# Ears_0603.net
KiCad netlist of a schematic drawn in EAGLE
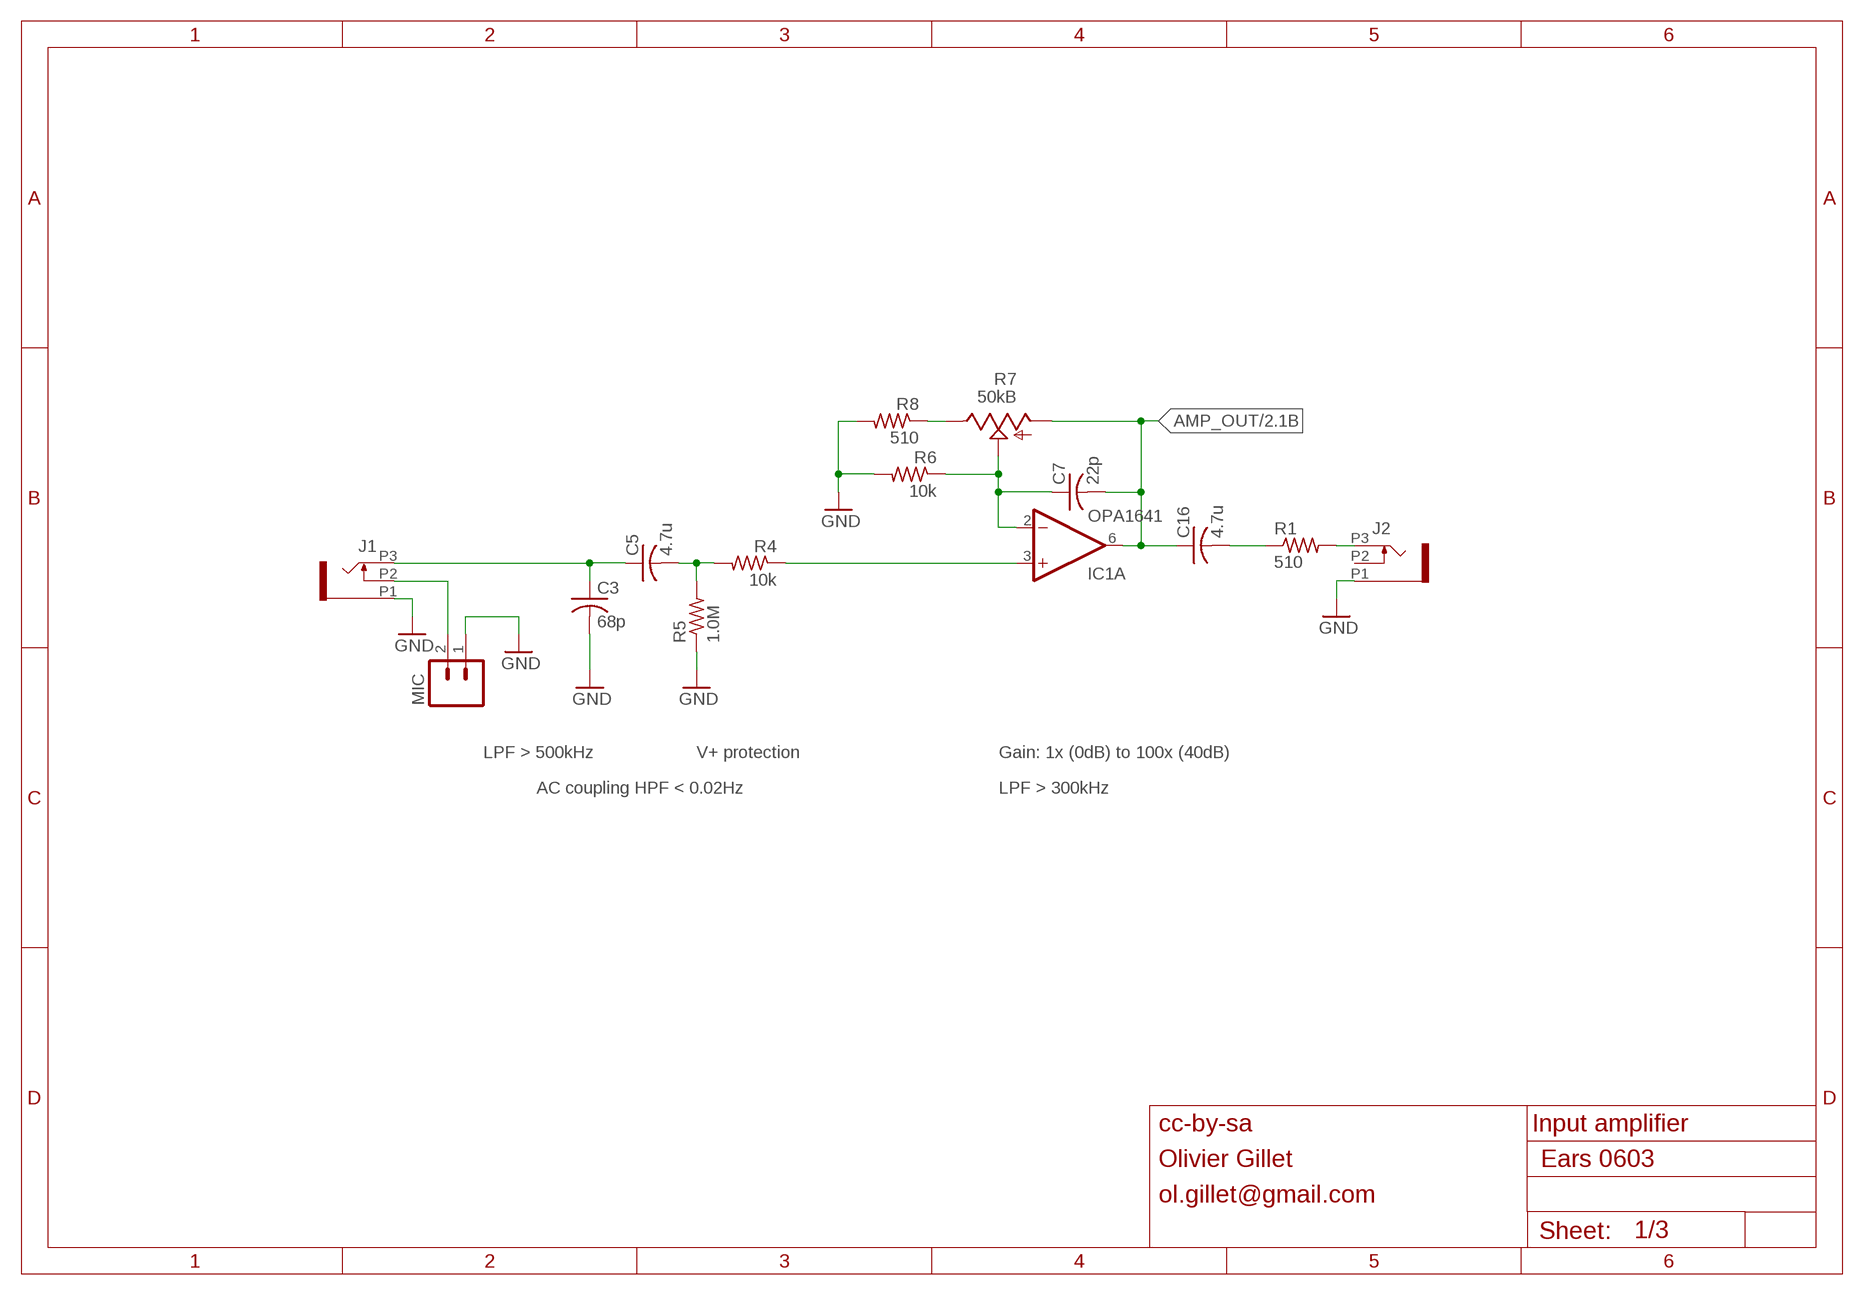
[diagram p0: schematic, sheet 1]
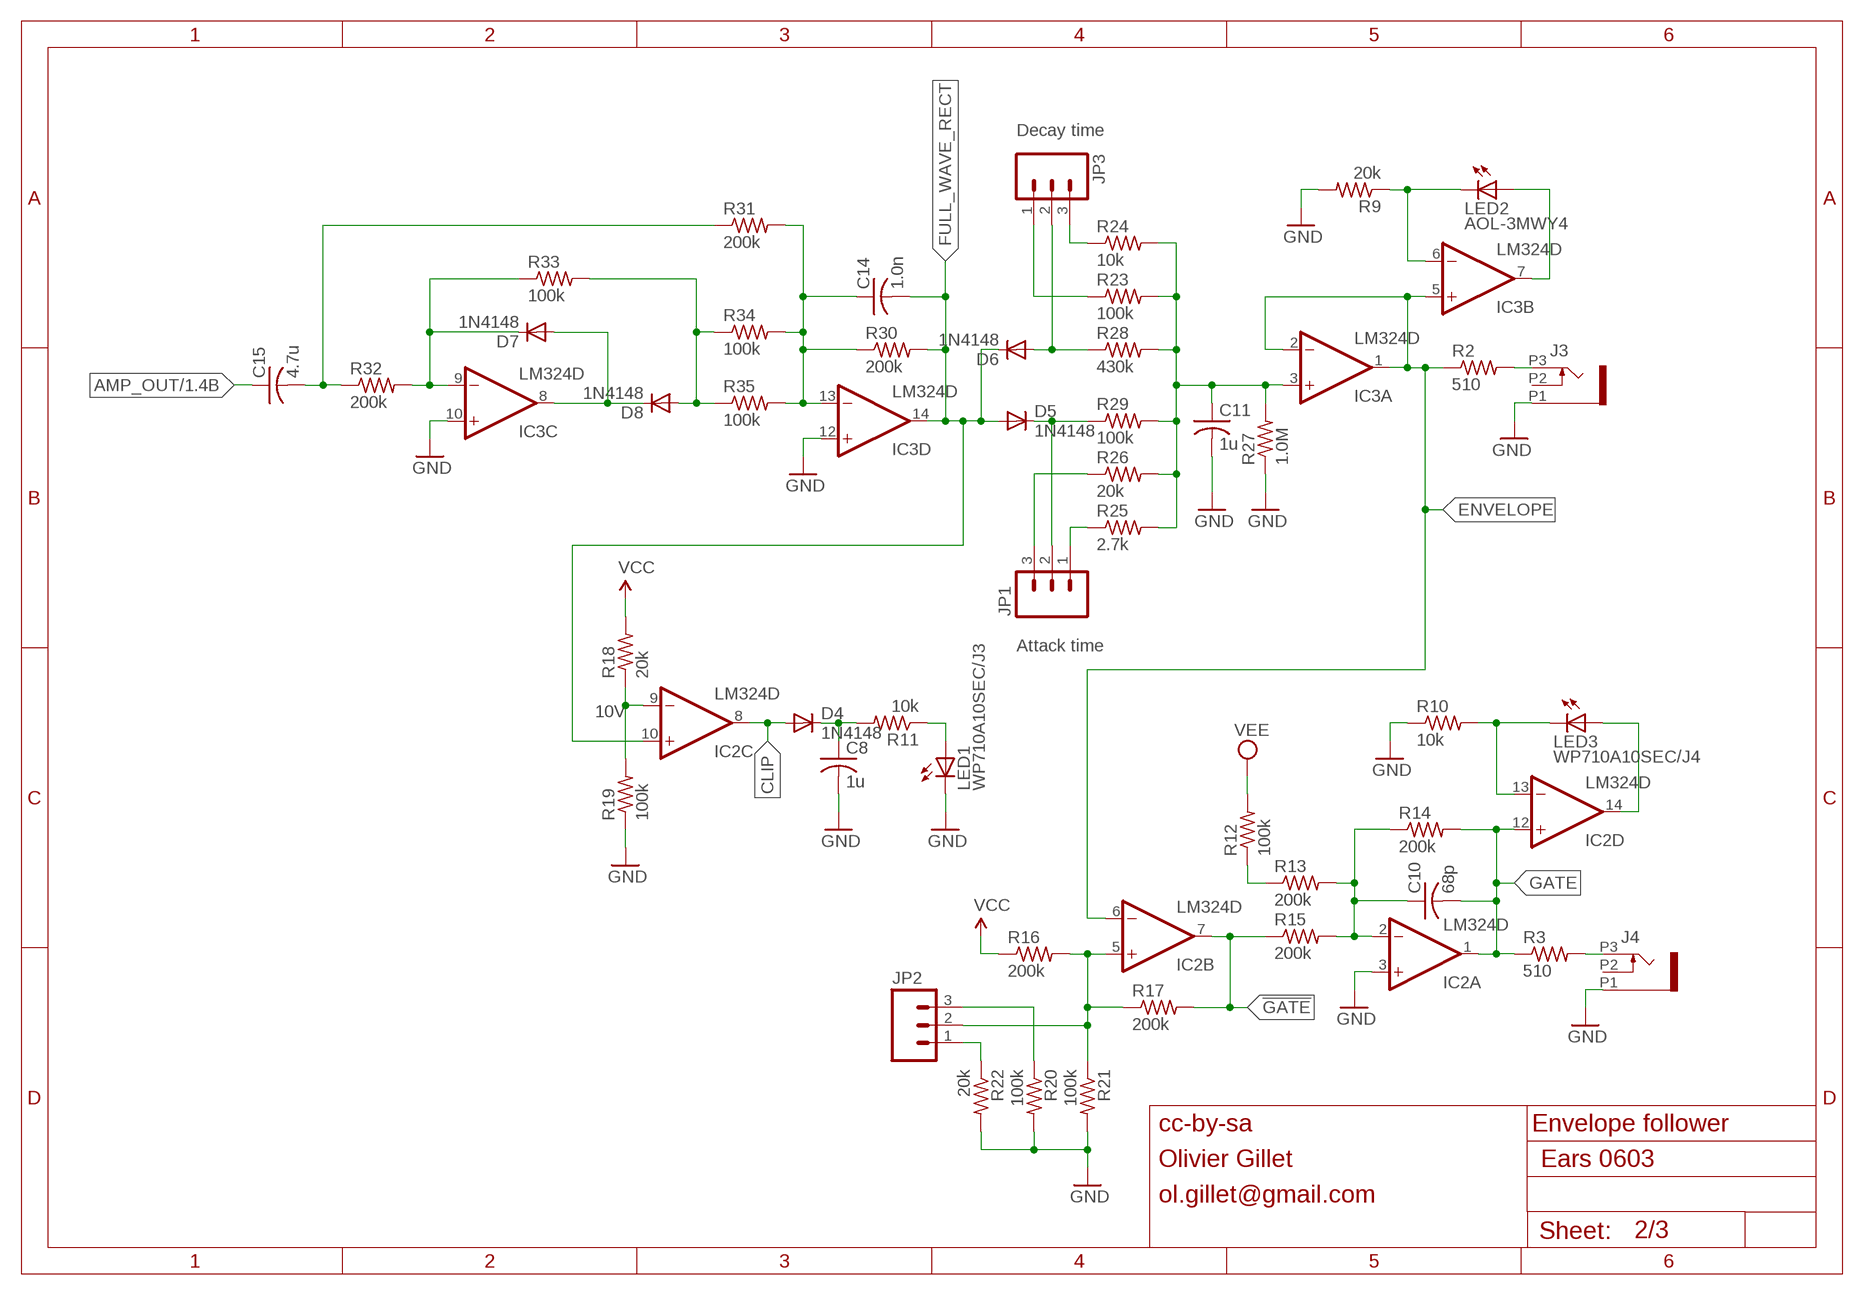
[diagram p1: schematic, sheet 2]
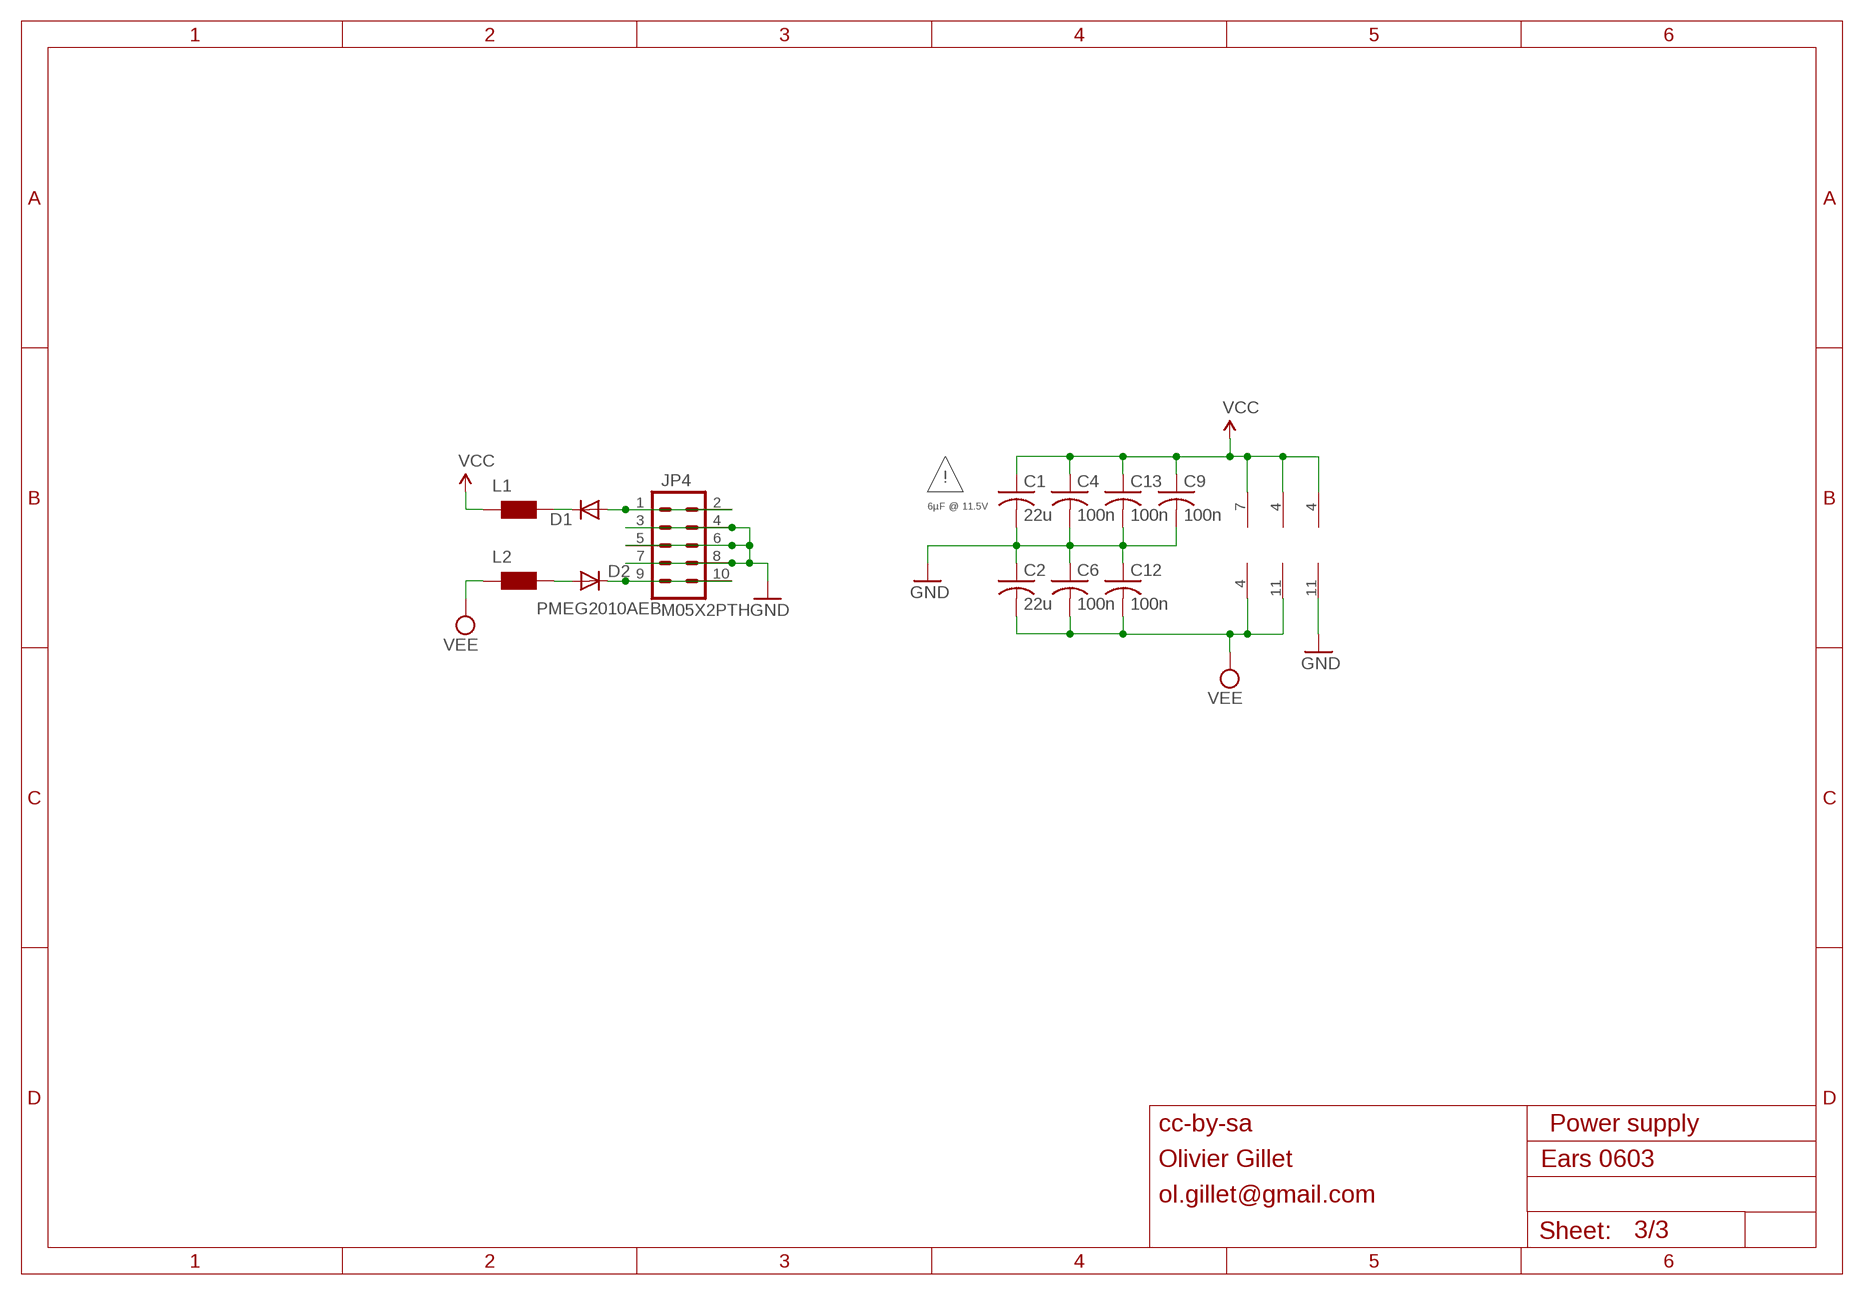
[diagram p2: schematic, sheet 3]

(export (version "E")
  (design (tool "Eeschema 10.0.6"))
  (components
    (comp (ref "C8")
      (value "1u")
      (footprint "eagle-import:C0603")
      (libsource (lib "eagle-import") (part "C-USC0603"))
    )
    (comp (ref "C10")
      (value "68p")
      (footprint "eagle-import:C0603")
      (libsource (lib "eagle-import") (part "C-USC0603"))
    )
    (comp (ref "C11")
      (value "1u")
      (footprint "eagle-import:C0603")
      (libsource (lib "eagle-import") (part "C-USC0603"))
    )
    (comp (ref "C14")
      (value "1.0n")
      (footprint "eagle-import:C0603")
      (libsource (lib "eagle-import") (part "C-USC0603"))
    )
    (comp (ref "C15")
      (value "4.7u")
      (footprint "eagle-import:C0603")
      (libsource (lib "eagle-import") (part "C-USC0603"))
    )
    (comp (ref "D4")
      (value "1N4148")
      (footprint "eagle-import:SOD323-W")
      (libsource (lib "eagle-import") (part "DIODE-SOD323-W"))
    )
    (comp (ref "D5")
      (value "1N4148")
      (footprint "eagle-import:SOD323-W")
      (libsource (lib "eagle-import") (part "DIODE-SOD323-W"))
    )
    (comp (ref "D6")
      (value "1N4148")
      (footprint "eagle-import:SOD323-W")
      (libsource (lib "eagle-import") (part "DIODE-SOD323-W"))
    )
    (comp (ref "D7")
      (value "1N4148")
      (footprint "eagle-import:SOD323-W")
      (libsource (lib "eagle-import") (part "DIODE-SOD323-W"))
    )
    (comp (ref "D8")
      (value "1N4148")
      (footprint "eagle-import:SOD323-W")
      (libsource (lib "eagle-import") (part "DIODE-SOD323-W"))
    )
    (comp (ref "IC2")
      (value "LM324D")
      (footprint "eagle-import:SO14")
      (libsource (lib "eagle-import") (part "LM324D"))
    )
    (comp (ref "IC3")
      (value "LM324D")
      (footprint "eagle-import:SO14")
      (libsource (lib "eagle-import") (part "LM324D"))
    )
    (comp (ref "J3")
      (value "PJ301_THONKICONN6")
      (footprint "eagle-import:WQP_PJ_301M6")
      (libsource (lib "eagle-import") (part "PJ301_THONKICONN6"))
    )
    (comp (ref "J4")
      (value "PJ301_THONKICONN6")
      (footprint "eagle-import:WQP_PJ_301M6")
      (libsource (lib "eagle-import") (part "PJ301_THONKICONN6"))
    )
    (comp (ref "JP1")
      (value "M03PTH")
      (footprint "eagle-import:1X03")
      (libsource (lib "eagle-import") (part "M03PTH"))
    )
    (comp (ref "JP2")
      (value "M03PTH")
      (footprint "eagle-import:1X03")
      (libsource (lib "eagle-import") (part "M03PTH"))
    )
    (comp (ref "JP3")
      (value "M03PTH")
      (footprint "eagle-import:1X03")
      (libsource (lib "eagle-import") (part "M03PTH"))
    )
    (comp (ref "LED1")
      (value "WP710A10SEC/J3")
      (footprint "eagle-import:LED3MM")
      (libsource (lib "eagle-import") (part "LED3MM"))
    )
    (comp (ref "LED2")
      (value "AOL-3MWY4")
      (footprint "eagle-import:LED3MM")
      (libsource (lib "eagle-import") (part "LED3MM"))
    )
    (comp (ref "LED3")
      (value "WP710A10SEC/J4")
      (footprint "eagle-import:LED3MM")
      (libsource (lib "eagle-import") (part "LED3MM"))
    )
    (comp (ref "R2")
      (value "510")
      (footprint "eagle-import:R0603")
      (libsource (lib "eagle-import") (part "R-US_R0603"))
    )
    (comp (ref "R3")
      (value "510")
      (footprint "eagle-import:R0603")
      (libsource (lib "eagle-import") (part "R-US_R0603"))
    )
    (comp (ref "R9")
      (value "20k")
      (footprint "eagle-import:R0603")
      (libsource (lib "eagle-import") (part "R-US_R0603"))
    )
    (comp (ref "R10")
      (value "10k")
      (footprint "eagle-import:R0603")
      (libsource (lib "eagle-import") (part "R-US_R0603"))
    )
    (comp (ref "R11")
      (value "10k")
      (footprint "eagle-import:R0603")
      (libsource (lib "eagle-import") (part "R-US_R0603"))
    )
    (comp (ref "R12")
      (value "100k")
      (footprint "eagle-import:R0603")
      (libsource (lib "eagle-import") (part "R-US_R0603"))
    )
    (comp (ref "R13")
      (value "200k")
      (footprint "eagle-import:R0603")
      (libsource (lib "eagle-import") (part "R-US_R0603"))
    )
    (comp (ref "R14")
      (value "200k")
      (footprint "eagle-import:R0603")
      (libsource (lib "eagle-import") (part "R-US_R0603"))
    )
    (comp (ref "R15")
      (value "200k")
      (footprint "eagle-import:R0603")
      (libsource (lib "eagle-import") (part "R-US_R0603"))
    )
    (comp (ref "R16")
      (value "200k")
      (footprint "eagle-import:R0603")
      (libsource (lib "eagle-import") (part "R-US_R0603"))
    )
    (comp (ref "R17")
      (value "200k")
      (footprint "eagle-import:R0603")
      (libsource (lib "eagle-import") (part "R-US_R0603"))
    )
    (comp (ref "R18")
      (value "20k")
      (footprint "eagle-import:R0603")
      (libsource (lib "eagle-import") (part "R-US_R0603"))
    )
    (comp (ref "R19")
      (value "100k")
      (footprint "eagle-import:R0603")
      (libsource (lib "eagle-import") (part "R-US_R0603"))
    )
    (comp (ref "R20")
      (value "100k")
      (footprint "eagle-import:R0603")
      (libsource (lib "eagle-import") (part "R-US_R0603"))
    )
    (comp (ref "R21")
      (value "100k")
      (footprint "eagle-import:R0603")
      (libsource (lib "eagle-import") (part "R-US_R0603"))
    )
    (comp (ref "R22")
      (value "20k")
      (footprint "eagle-import:R0603")
      (libsource (lib "eagle-import") (part "R-US_R0603"))
    )
    (comp (ref "R23")
      (value "100k")
      (footprint "eagle-import:R0603")
      (libsource (lib "eagle-import") (part "R-US_R0603"))
    )
    (comp (ref "R24")
      (value "10k")
      (footprint "eagle-import:R0603")
      (libsource (lib "eagle-import") (part "R-US_R0603"))
    )
    (comp (ref "R25")
      (value "2.7k")
      (footprint "eagle-import:R0603")
      (libsource (lib "eagle-import") (part "R-US_R0603"))
    )
    (comp (ref "R26")
      (value "20k")
      (footprint "eagle-import:R0603")
      (libsource (lib "eagle-import") (part "R-US_R0603"))
    )
    (comp (ref "R27")
      (value "1.0M")
      (footprint "eagle-import:R0603")
      (libsource (lib "eagle-import") (part "R-US_R0603"))
    )
    (comp (ref "R28")
      (value "430k")
      (footprint "eagle-import:R0603")
      (libsource (lib "eagle-import") (part "R-US_R0603"))
    )
    (comp (ref "R29")
      (value "100k")
      (footprint "eagle-import:R0603")
      (libsource (lib "eagle-import") (part "R-US_R0603"))
    )
    (comp (ref "R30")
      (value "200k")
      (footprint "eagle-import:R0603")
      (libsource (lib "eagle-import") (part "R-US_R0603"))
    )
    (comp (ref "R31")
      (value "200k")
      (footprint "eagle-import:R0603")
      (libsource (lib "eagle-import") (part "R-US_R0603"))
    )
    (comp (ref "R32")
      (value "200k")
      (footprint "eagle-import:R0603")
      (libsource (lib "eagle-import") (part "R-US_R0603"))
    )
    (comp (ref "R33")
      (value "100k")
      (footprint "eagle-import:R0603")
      (libsource (lib "eagle-import") (part "R-US_R0603"))
    )
    (comp (ref "R34")
      (value "100k")
      (footprint "eagle-import:R0603")
      (libsource (lib "eagle-import") (part "R-US_R0603"))
    )
    (comp (ref "R35")
      (value "100k")
      (footprint "eagle-import:R0603")
      (libsource (lib "eagle-import") (part "R-US_R0603"))
    )
    (comp (ref "C1")
      (value "22u")
      (footprint "eagle-import:C1206")
      (libsource (lib "eagle-import") (part "C-USC1206"))
    )
    (comp (ref "C2")
      (value "22u")
      (footprint "eagle-import:C1206")
      (libsource (lib "eagle-import") (part "C-USC1206"))
    )
    (comp (ref "C4")
      (value "100n")
      (footprint "eagle-import:C0603")
      (libsource (lib "eagle-import") (part "C-USC0603"))
    )
    (comp (ref "C6")
      (value "100n")
      (footprint "eagle-import:C0603")
      (libsource (lib "eagle-import") (part "C-USC0603"))
    )
    (comp (ref "C9")
      (value "100n")
      (footprint "eagle-import:C0603")
      (libsource (lib "eagle-import") (part "C-USC0603"))
    )
    (comp (ref "C12")
      (value "100n")
      (footprint "eagle-import:C0603")
      (libsource (lib "eagle-import") (part "C-USC0603"))
    )
    (comp (ref "C13")
      (value "100n")
      (footprint "eagle-import:C0603")
      (libsource (lib "eagle-import") (part "C-USC0603"))
    )
    (comp (ref "D1")
      (value "PMEG2010AEB")
      (footprint "eagle-import:SOD323-W")
      (libsource (lib "eagle-import") (part "DIODE-SOD323-W"))
    )
    (comp (ref "D2")
      (value "PMEG2010AEB")
      (footprint "eagle-import:SOD323-W")
      (libsource (lib "eagle-import") (part "DIODE-SOD323-W"))
    )
    (comp (ref "IC1")
      (value "OPA1641")
      (footprint "eagle-import:MSOP8")
      (libsource (lib "eagle-import") (part "OPA1641"))
    )
    (comp (ref "JP4")
      (value "M05X2PTH")
      (footprint "eagle-import:AVR_ICSP")
      (libsource (lib "eagle-import") (part "M05X2PTH"))
    )
    (comp (ref "L1")
      (value "WE-CBF_0603")
      (footprint "eagle-import:0603")
      (libsource (lib "eagle-import") (part "WE-CBF_0603"))
    )
    (comp (ref "L2")
      (value "WE-CBF_0603")
      (footprint "eagle-import:0603")
      (libsource (lib "eagle-import") (part "WE-CBF_0603"))
    )
    (comp (ref "C3")
      (value "68p")
      (footprint "eagle-import:C0603")
      (libsource (lib "eagle-import") (part "C-USC0603"))
    )
    (comp (ref "C5")
      (value "4.7u")
      (footprint "eagle-import:C0603")
      (libsource (lib "eagle-import") (part "C-USC0603"))
    )
    (comp (ref "C7")
      (value "22p")
      (footprint "eagle-import:C0603")
      (libsource (lib "eagle-import") (part "C-USC0603"))
    )
    (comp (ref "C16")
      (value "4.7u")
      (footprint "eagle-import:C0603")
      (libsource (lib "eagle-import") (part "C-USC0603"))
    )
    (comp (ref "J1")
      (value "PJ301_THONKICONN6")
      (footprint "eagle-import:WQP_PJ_301M6")
      (libsource (lib "eagle-import") (part "PJ301_THONKICONN6"))
    )
    (comp (ref "J2")
      (value "PJ301_THONKICONN6")
      (footprint "eagle-import:WQP_PJ_301M6")
      (libsource (lib "eagle-import") (part "PJ301_THONKICONN6"))
    )
    (comp (ref "MIC")
      (value "M02TINY")
      (footprint "eagle-import:1X02_TINY")
      (libsource (lib "eagle-import") (part "M02TINY"))
    )
    (comp (ref "R1")
      (value "510")
      (footprint "eagle-import:R0603")
      (libsource (lib "eagle-import") (part "R-US_R0603"))
    )
    (comp (ref "R4")
      (value "10k")
      (footprint "eagle-import:R0603")
      (libsource (lib "eagle-import") (part "R-US_R0603"))
    )
    (comp (ref "R5")
      (value "1.0M")
      (footprint "eagle-import:R0603")
      (libsource (lib "eagle-import") (part "R-US_R0603"))
    )
    (comp (ref "R6")
      (value "10k")
      (footprint "eagle-import:R0603")
      (libsource (lib "eagle-import") (part "R-US_R0603"))
    )
    (comp (ref "R7")
      (value "50kB")
      (footprint "eagle-import:ALPS_POT_VERTICAL_PS")
      (libsource (lib "eagle-import") (part "POT_USVERTICAL_PS"))
    )
    (comp (ref "R8")
      (value "510")
      (footprint "eagle-import:R0603")
      (libsource (lib "eagle-import") (part "R-US_R0603"))
    )
  )
  (nets
    (net (code "1") (name "AMP_OUT") (class "Default")
      (node (ref "C15") (pin "1") (pinfunction "1_1") (pintype "passive"))
      (node (ref "C16") (pin "1") (pinfunction "1_1") (pintype "passive"))
      (node (ref "C7") (pin "2") (pinfunction "2_2") (pintype "passive"))
      (node (ref "IC1") (pin "6") (pinfunction "OUT_6") (pintype "output"))
      (node (ref "R7") (pin "P$3") (pinfunction "A_P$3") (pintype "passive"))
    )
    (net (code "2") (name "CLIP") (class "Default")
      (node (ref "D4") (pin "A") (pinfunction "A_A") (pintype "passive"))
      (node (ref "IC2") (pin "8") (pinfunction "OUT_8") (pintype "output"))
    )
    (net (code "3") (name "ENVELOPE") (class "Default")
      (node (ref "IC2") (pin "6") (pinfunction "-IN_6") (pintype "input"))
      (node (ref "IC3") (pin "1") (pinfunction "OUT_1") (pintype "output"))
      (node (ref "IC3") (pin "2") (pinfunction "-IN_2") (pintype "input"))
      (node (ref "IC3") (pin "5") (pinfunction "+IN_5") (pintype "input"))
      (node (ref "R2") (pin "1") (pinfunction "1_1") (pintype "passive"))
    )
    (net (code "4") (name "FULL_WAVE_RECT") (class "Default")
      (node (ref "C14") (pin "2") (pinfunction "2_2") (pintype "passive"))
      (node (ref "D5") (pin "A") (pinfunction "A_A") (pintype "passive"))
      (node (ref "D6") (pin "C") (pinfunction "C_C") (pintype "passive"))
      (node (ref "IC2") (pin "10") (pinfunction "+IN_10") (pintype "input"))
      (node (ref "IC3") (pin "14") (pinfunction "OUT_14") (pintype "output"))
      (node (ref "R30") (pin "2") (pinfunction "2_2") (pintype "passive"))
    )
    (net (code "5") (name "GATE") (class "Default")
      (node (ref "C10") (pin "2") (pinfunction "2_2") (pintype "passive"))
      (node (ref "IC2") (pin "1") (pinfunction "OUT_1") (pintype "output"))
      (node (ref "IC2") (pin "12") (pinfunction "+IN_12") (pintype "input"))
      (node (ref "R14") (pin "2") (pinfunction "2_2") (pintype "passive"))
      (node (ref "R3") (pin "1") (pinfunction "1_1") (pintype "passive"))
    )
    (net (code "6") (name "GND") (class "Default")
      (node (ref "C1") (pin "2") (pinfunction "2_2") (pintype "passive"))
      (node (ref "C11") (pin "2") (pinfunction "2_2") (pintype "passive"))
      (node (ref "C12") (pin "1") (pinfunction "1_1") (pintype "passive"))
      (node (ref "C13") (pin "2") (pinfunction "2_2") (pintype "passive"))
      (node (ref "C2") (pin "1") (pinfunction "1_1") (pintype "passive"))
      (node (ref "C3") (pin "2") (pinfunction "2_2") (pintype "passive"))
      (node (ref "C4") (pin "2") (pinfunction "2_2") (pintype "passive"))
      (node (ref "C6") (pin "1") (pinfunction "1_1") (pintype "passive"))
      (node (ref "C8") (pin "2") (pinfunction "2_2") (pintype "passive"))
      (node (ref "C9") (pin "2") (pinfunction "2_2") (pintype "passive"))
      (node (ref "IC2") (pin "11") (pinfunction "V-_11") (pintype "power_in"))
      (node (ref "IC2") (pin "3") (pinfunction "+IN_3") (pintype "input"))
      (node (ref "IC3") (pin "10") (pinfunction "+IN_10") (pintype "input"))
      (node (ref "IC3") (pin "12") (pinfunction "+IN_12") (pintype "input"))
      (node (ref "J1") (pin "P1") (pinfunction "1_P1") (pintype "passive"))
      (node (ref "J2") (pin "P1") (pinfunction "1_P1") (pintype "passive"))
      (node (ref "J3") (pin "P1") (pinfunction "1_P1") (pintype "passive"))
      (node (ref "J4") (pin "P1") (pinfunction "1_P1") (pintype "passive"))
      (node (ref "JP4") (pin "3") (pinfunction "3_3") (pintype "passive"))
      (node (ref "JP4") (pin "4") (pinfunction "4_4") (pintype "passive"))
      (node (ref "JP4") (pin "5") (pinfunction "5_5") (pintype "passive"))
      (node (ref "JP4") (pin "6") (pinfunction "6_6") (pintype "passive"))
      (node (ref "JP4") (pin "7") (pinfunction "7_7") (pintype "passive"))
      (node (ref "JP4") (pin "8") (pinfunction "8_8") (pintype "passive"))
      (node (ref "LED1") (pin "K") (pinfunction "C_K") (pintype "passive"))
      (node (ref "MIC") (pin "1") (pinfunction "1_1") (pintype "passive"))
      (node (ref "R10") (pin "1") (pinfunction "1_1") (pintype "passive"))
      (node (ref "R19") (pin "1") (pinfunction "1_1") (pintype "passive"))
      (node (ref "R20") (pin "2") (pinfunction "2_2") (pintype "passive"))
      (node (ref "R21") (pin "2") (pinfunction "2_2") (pintype "passive"))
      (node (ref "R22") (pin "2") (pinfunction "2_2") (pintype "passive"))
      (node (ref "R27") (pin "1") (pinfunction "1_1") (pintype "passive"))
      (node (ref "R5") (pin "1") (pinfunction "1_1") (pintype "passive"))
      (node (ref "R6") (pin "2") (pinfunction "2_2") (pintype "passive"))
      (node (ref "R8") (pin "2") (pinfunction "2_2") (pintype "passive"))
      (node (ref "R9") (pin "2") (pinfunction "2_2") (pintype "passive"))
    )
    (net (code "7") (name "Net-(C5-Pad2)") (class "Default")
      (node (ref "C5") (pin "2") (pinfunction "2_2") (pintype "passive"))
      (node (ref "R4") (pin "2") (pinfunction "2_2") (pintype "passive"))
      (node (ref "R5") (pin "2") (pinfunction "2_2") (pintype "passive"))
    )
    (net (code "8") (name "Net-(C8-Pad1)") (class "Default")
      (node (ref "C8") (pin "1") (pinfunction "1_1") (pintype "passive"))
      (node (ref "D4") (pin "C") (pinfunction "C_C") (pintype "passive"))
      (node (ref "R11") (pin "2") (pinfunction "2_2") (pintype "passive"))
    )
    (net (code "9") (name "Net-(C15-Pad2)") (class "Default")
      (node (ref "C15") (pin "2") (pinfunction "2_2") (pintype "passive"))
      (node (ref "R31") (pin "1") (pinfunction "1_1") (pintype "passive"))
      (node (ref "R32") (pin "1") (pinfunction "1_1") (pintype "passive"))
    )
    (net (code "10") (name "Net-(C16-Pad2)") (class "Default")
      (node (ref "C16") (pin "2") (pinfunction "2_2") (pintype "passive"))
      (node (ref "R1") (pin "1") (pinfunction "1_1") (pintype "passive"))
    )
    (net (code "11") (name "Net-(D1-PadA)") (class "Default")
      (node (ref "D1") (pin "A") (pinfunction "A_A") (pintype "passive"))
      (node (ref "JP4") (pin "1") (pinfunction "1_1") (pintype "passive"))
      (node (ref "JP4") (pin "2") (pinfunction "2_2") (pintype "passive"))
    )
    (net (code "12") (name "Net-(D1-PadC)") (class "Default")
      (node (ref "D1") (pin "C") (pinfunction "C_C") (pintype "passive"))
      (node (ref "L1") (pin "2") (pinfunction "2_2") (pintype "passive"))
    )
    (net (code "13") (name "Net-(D2-PadA)") (class "Default")
      (node (ref "D2") (pin "A") (pinfunction "A_A") (pintype "passive"))
      (node (ref "L2") (pin "2") (pinfunction "2_2") (pintype "passive"))
    )
    (net (code "14") (name "Net-(D2-PadC)") (class "Default")
      (node (ref "D2") (pin "C") (pinfunction "C_C") (pintype "passive"))
      (node (ref "JP4") (pin "10") (pinfunction "10_10") (pintype "passive"))
      (node (ref "JP4") (pin "9") (pinfunction "9_9") (pintype "passive"))
    )
    (net (code "15") (name "Net-(D5-PadC)") (class "Default")
      (node (ref "D5") (pin "C") (pinfunction "C_C") (pintype "passive"))
      (node (ref "JP1") (pin "2") (pinfunction "2_2") (pintype "passive"))
      (node (ref "R29") (pin "1") (pinfunction "1_1") (pintype "passive"))
    )
    (net (code "16") (name "Net-(D6-PadA)") (class "Default")
      (node (ref "D6") (pin "A") (pinfunction "A_A") (pintype "passive"))
      (node (ref "JP3") (pin "2") (pinfunction "2_2") (pintype "passive"))
      (node (ref "R28") (pin "1") (pinfunction "1_1") (pintype "passive"))
    )
    (net (code "17") (name "Net-(D8-PadA)") (class "Default")
      (node (ref "D8") (pin "A") (pinfunction "A_A") (pintype "passive"))
      (node (ref "R33") (pin "2") (pinfunction "2_2") (pintype "passive"))
      (node (ref "R34") (pin "1") (pinfunction "1_1") (pintype "passive"))
      (node (ref "R35") (pin "1") (pinfunction "1_1") (pintype "passive"))
    )
    (net (code "18") (name "Net-(IC1A-+IN)") (class "Default")
      (node (ref "IC1") (pin "3") (pinfunction "+IN_3") (pintype "input"))
      (node (ref "R4") (pin "1") (pinfunction "1_1") (pintype "passive"))
    )
    (net (code "19") (name "Net-(IC1A--IN)") (class "Default")
      (node (ref "C7") (pin "1") (pinfunction "1_1") (pintype "passive"))
      (node (ref "IC1") (pin "2") (pinfunction "-IN_2") (pintype "input"))
      (node (ref "R6") (pin "1") (pinfunction "1_1") (pintype "passive"))
      (node (ref "R7") (pin "P$2") (pinfunction "S_P$2") (pintype "passive"))
    )
    (net (code "20") (name "Net-(IC2A--IN)") (class "Default")
      (node (ref "C10") (pin "1") (pinfunction "1_1") (pintype "passive"))
      (node (ref "IC2") (pin "2") (pinfunction "-IN_2") (pintype "input"))
      (node (ref "R13") (pin "2") (pinfunction "2_2") (pintype "passive"))
      (node (ref "R14") (pin "1") (pinfunction "1_1") (pintype "passive"))
      (node (ref "R15") (pin "2") (pinfunction "2_2") (pintype "passive"))
    )
    (net (code "21") (name "Net-(IC2B-+IN)") (class "Default")
      (node (ref "IC2") (pin "5") (pinfunction "+IN_5") (pintype "input"))
      (node (ref "JP2") (pin "2") (pinfunction "2_2") (pintype "passive"))
      (node (ref "R16") (pin "2") (pinfunction "2_2") (pintype "passive"))
      (node (ref "R17") (pin "1") (pinfunction "1_1") (pintype "passive"))
      (node (ref "R21") (pin "1") (pinfunction "1_1") (pintype "passive"))
    )
    (net (code "22") (name "Net-(IC2C--IN)") (class "Default")
      (node (ref "IC2") (pin "9") (pinfunction "-IN_9") (pintype "input"))
      (node (ref "R18") (pin "1") (pinfunction "1_1") (pintype "passive"))
      (node (ref "R19") (pin "2") (pinfunction "2_2") (pintype "passive"))
    )
    (net (code "23") (name "Net-(IC2D--IN)") (class "Default")
      (node (ref "IC2") (pin "13") (pinfunction "-IN_13") (pintype "input"))
      (node (ref "LED3") (pin "K") (pinfunction "C_K") (pintype "passive"))
      (node (ref "R10") (pin "2") (pinfunction "2_2") (pintype "passive"))
    )
    (net (code "24") (name "Net-(IC2D-OUT)") (class "Default")
      (node (ref "IC2") (pin "14") (pinfunction "OUT_14") (pintype "output"))
      (node (ref "LED3") (pin "A") (pinfunction "A_A") (pintype "passive"))
    )
    (net (code "25") (name "Net-(IC3A-+IN)") (class "Default")
      (node (ref "C11") (pin "1") (pinfunction "1_1") (pintype "passive"))
      (node (ref "IC3") (pin "3") (pinfunction "+IN_3") (pintype "input"))
      (node (ref "R23") (pin "2") (pinfunction "2_2") (pintype "passive"))
      (node (ref "R24") (pin "2") (pinfunction "2_2") (pintype "passive"))
      (node (ref "R25") (pin "2") (pinfunction "2_2") (pintype "passive"))
      (node (ref "R26") (pin "2") (pinfunction "2_2") (pintype "passive"))
      (node (ref "R27") (pin "2") (pinfunction "2_2") (pintype "passive"))
      (node (ref "R28") (pin "2") (pinfunction "2_2") (pintype "passive"))
      (node (ref "R29") (pin "2") (pinfunction "2_2") (pintype "passive"))
    )
    (net (code "26") (name "Net-(IC3B--IN)") (class "Default")
      (node (ref "IC3") (pin "6") (pinfunction "-IN_6") (pintype "input"))
      (node (ref "LED2") (pin "K") (pinfunction "C_K") (pintype "passive"))
      (node (ref "R9") (pin "1") (pinfunction "1_1") (pintype "passive"))
    )
    (net (code "27") (name "Net-(IC3B-OUT)") (class "Default")
      (node (ref "IC3") (pin "7") (pinfunction "OUT_7") (pintype "output"))
      (node (ref "LED2") (pin "A") (pinfunction "A_A") (pintype "passive"))
    )
    (net (code "28") (name "Net-(IC3C--IN)") (class "Default")
      (node (ref "D7") (pin "C") (pinfunction "C_C") (pintype "passive"))
      (node (ref "IC3") (pin "9") (pinfunction "-IN_9") (pintype "input"))
      (node (ref "R32") (pin "2") (pinfunction "2_2") (pintype "passive"))
      (node (ref "R33") (pin "1") (pinfunction "1_1") (pintype "passive"))
    )
    (net (code "29") (name "Net-(IC3C-OUT)") (class "Default")
      (node (ref "D7") (pin "A") (pinfunction "A_A") (pintype "passive"))
      (node (ref "D8") (pin "C") (pinfunction "C_C") (pintype "passive"))
      (node (ref "IC3") (pin "8") (pinfunction "OUT_8") (pintype "output"))
    )
    (net (code "30") (name "Net-(IC3D--IN)") (class "Default")
      (node (ref "C14") (pin "1") (pinfunction "1_1") (pintype "passive"))
      (node (ref "IC3") (pin "13") (pinfunction "-IN_13") (pintype "input"))
      (node (ref "R30") (pin "1") (pinfunction "1_1") (pintype "passive"))
      (node (ref "R31") (pin "2") (pinfunction "2_2") (pintype "passive"))
      (node (ref "R34") (pin "2") (pinfunction "2_2") (pintype "passive"))
      (node (ref "R35") (pin "2") (pinfunction "2_2") (pintype "passive"))
    )
    (net (code "31") (name "Net-(J1-2)") (class "Default")
      (node (ref "J1") (pin "P2") (pinfunction "2_P2") (pintype "passive"))
      (node (ref "MIC") (pin "2") (pinfunction "2_2") (pintype "passive"))
    )
    (net (code "32") (name "Net-(J1-3)") (class "Default")
      (node (ref "C3") (pin "1") (pinfunction "1_1") (pintype "passive"))
      (node (ref "C5") (pin "1") (pinfunction "1_1") (pintype "passive"))
      (node (ref "J1") (pin "P3") (pinfunction "3_P3") (pintype "passive"))
    )
    (net (code "33") (name "Net-(J2-3)") (class "Default")
      (node (ref "J2") (pin "P3") (pinfunction "3_P3") (pintype "passive"))
      (node (ref "R1") (pin "2") (pinfunction "2_2") (pintype "passive"))
    )
    (net (code "34") (name "Net-(J3-3)") (class "Default")
      (node (ref "J3") (pin "P3") (pinfunction "3_P3") (pintype "passive"))
      (node (ref "R2") (pin "2") (pinfunction "2_2") (pintype "passive"))
    )
    (net (code "35") (name "Net-(J4-3)") (class "Default")
      (node (ref "J4") (pin "P3") (pinfunction "3_P3") (pintype "passive"))
      (node (ref "R3") (pin "2") (pinfunction "2_2") (pintype "passive"))
    )
    (net (code "36") (name "Net-(JP1-Pad1)") (class "Default")
      (node (ref "JP1") (pin "1") (pinfunction "1_1") (pintype "passive"))
      (node (ref "R25") (pin "1") (pinfunction "1_1") (pintype "passive"))
    )
    (net (code "37") (name "Net-(JP1-Pad3)") (class "Default")
      (node (ref "JP1") (pin "3") (pinfunction "3_3") (pintype "passive"))
      (node (ref "R26") (pin "1") (pinfunction "1_1") (pintype "passive"))
    )
    (net (code "38") (name "Net-(JP2-Pad1)") (class "Default")
      (node (ref "JP2") (pin "1") (pinfunction "1_1") (pintype "passive"))
      (node (ref "R22") (pin "1") (pinfunction "1_1") (pintype "passive"))
    )
    (net (code "39") (name "Net-(JP2-Pad3)") (class "Default")
      (node (ref "JP2") (pin "3") (pinfunction "3_3") (pintype "passive"))
      (node (ref "R20") (pin "1") (pinfunction "1_1") (pintype "passive"))
    )
    (net (code "40") (name "Net-(JP3-Pad1)") (class "Default")
      (node (ref "JP3") (pin "1") (pinfunction "1_1") (pintype "passive"))
      (node (ref "R23") (pin "1") (pinfunction "1_1") (pintype "passive"))
    )
    (net (code "41") (name "Net-(JP3-Pad3)") (class "Default")
      (node (ref "JP3") (pin "3") (pinfunction "3_3") (pintype "passive"))
      (node (ref "R24") (pin "1") (pinfunction "1_1") (pintype "passive"))
    )
    (net (code "42") (name "Net-(LED1-PadA)") (class "Default")
      (node (ref "LED1") (pin "A") (pinfunction "A_A") (pintype "passive"))
      (node (ref "R11") (pin "1") (pinfunction "1_1") (pintype "passive"))
    )
    (net (code "43") (name "Net-(R7-E)") (class "Default")
      (node (ref "R7") (pin "P$1") (pinfunction "E_P$1") (pintype "passive"))
      (node (ref "R8") (pin "1") (pinfunction "1_1") (pintype "passive"))
    )
    (net (code "44") (name "Net-(R12-Pad1)") (class "Default")
      (node (ref "R12") (pin "1") (pinfunction "1_1") (pintype "passive"))
      (node (ref "R13") (pin "1") (pinfunction "1_1") (pintype "passive"))
    )
    (net (code "45") (name "VCC") (class "Default")
      (node (ref "C1") (pin "1") (pinfunction "1_1") (pintype "passive"))
      (node (ref "C13") (pin "1") (pinfunction "1_1") (pintype "passive"))
      (node (ref "C4") (pin "1") (pinfunction "1_1") (pintype "passive"))
      (node (ref "C9") (pin "1") (pinfunction "1_1") (pintype "passive"))
      (node (ref "IC1") (pin "7") (pinfunction "V+_7") (pintype "power_in"))
      (node (ref "IC2") (pin "4") (pinfunction "V+_4") (pintype "power_in"))
      (node (ref "IC3") (pin "4") (pinfunction "V+_4") (pintype "power_in"))
      (node (ref "L1") (pin "1") (pinfunction "1_1") (pintype "passive"))
      (node (ref "R16") (pin "1") (pinfunction "1_1") (pintype "passive"))
      (node (ref "R18") (pin "2") (pinfunction "2_2") (pintype "passive"))
    )
    (net (code "46") (name "VEE") (class "Default")
      (node (ref "C12") (pin "2") (pinfunction "2_2") (pintype "passive"))
      (node (ref "C2") (pin "2") (pinfunction "2_2") (pintype "passive"))
      (node (ref "C6") (pin "2") (pinfunction "2_2") (pintype "passive"))
      (node (ref "IC1") (pin "4") (pinfunction "V-_4") (pintype "power_in"))
      (node (ref "IC3") (pin "11") (pinfunction "V-_11") (pintype "power_in"))
      (node (ref "L2") (pin "1") (pinfunction "1_1") (pintype "passive"))
      (node (ref "R12") (pin "2") (pinfunction "2_2") (pintype "passive"))
    )
    (net (code "47") (name "unconnected-(J2-2-PadP2)") (class "Default")
      (node (ref "J2") (pin "P2") (pinfunction "2_P2") (pintype "passive"))
    )
    (net (code "48") (name "unconnected-(J3-2-PadP2)") (class "Default")
      (node (ref "J3") (pin "P2") (pinfunction "2_P2") (pintype "passive"))
    )
    (net (code "49") (name "unconnected-(J4-2-PadP2)") (class "Default")
      (node (ref "J4") (pin "P2") (pinfunction "2_P2") (pintype "passive"))
    )
    (net (code "50") (name "~{GATE}") (class "Default")
      (node (ref "IC2") (pin "7") (pinfunction "OUT_7") (pintype "output"))
      (node (ref "R15") (pin "1") (pinfunction "1_1") (pintype "passive"))
      (node (ref "R17") (pin "2") (pinfunction "2_2") (pintype "passive"))
    )
  )
)
